# wifischematic.net
KiCad netlist of a schematic drawn in EAGLE
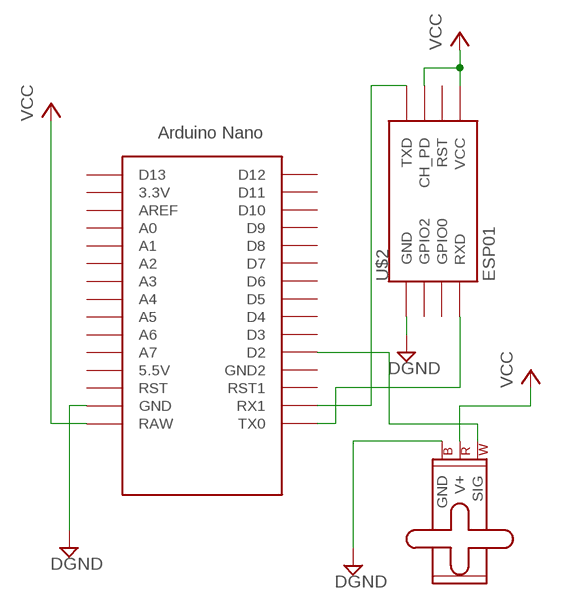
[diagram p0: schematic, sheet 1]

(export (version "E")
  (design (tool "Eeschema 10.0.6"))
  (components
    (comp (ref "M1")
      (value "SMALL_SERVO")
      (footprint "eagle-import:1X03")
      (libsource (lib "eagle-import") (part "SMALL_SERVO"))
    )
    (comp (ref "U$1")
      (value "NANO")
      (footprint "eagle-import:NANO")
      (libsource (lib "eagle-import") (part "NANO"))
    )
    (comp (ref "U$2")
      (value "ESP01")
      (footprint "eagle-import:ESP01")
      (libsource (lib "eagle-import") (part "ESP01"))
    )
  )
  (nets
    (net (code "1") (name "DGND") (class "Default")
      (node (ref "M1") (pin "3") (pinfunction "GND_3") (pintype "bidirectional"))
      (node (ref "U$1") (pin "GND") (pinfunction "GND_GND") (pintype "bidirectional"))
      (node (ref "U$2") (pin "GND") (pinfunction "GND_GND") (pintype "bidirectional"))
    )
    (net (code "2") (name "Net-(M1-SIG)") (class "Default")
      (node (ref "M1") (pin "1") (pinfunction "SIG_1") (pintype "bidirectional"))
      (node (ref "U$1") (pin "D2") (pinfunction "D2_D2") (pintype "bidirectional"))
    )
    (net (code "3") (name "Net-(U$2-RXD)") (class "Default")
      (node (ref "U$1") (pin "TX0") (pinfunction "TX0_TX0") (pintype "bidirectional"))
      (node (ref "U$2") (pin "RX") (pinfunction "RXD_RX") (pintype "bidirectional"))
    )
    (net (code "4") (name "Net-(U$2-TXD)") (class "Default")
      (node (ref "U$1") (pin "RX1") (pinfunction "RX1_RX1") (pintype "bidirectional"))
      (node (ref "U$2") (pin "TX") (pinfunction "TXD_TX") (pintype "bidirectional"))
    )
    (net (code "5") (name "VCC") (class "Default")
      (node (ref "M1") (pin "2") (pinfunction "V+_2") (pintype "bidirectional"))
      (node (ref "U$1") (pin "RAW") (pinfunction "RAW_RAW") (pintype "bidirectional"))
      (node (ref "U$2") (pin "CH_PD") (pinfunction "CH_PD_CH_PD") (pintype "bidirectional"))
      (node (ref "U$2") (pin "VCC") (pinfunction "VCC_VCC") (pintype "bidirectional"))
    )
    (net (code "6") (name "unconnected-(U$1-5.5V-Pad5V)") (class "Default")
      (node (ref "U$1") (pin "5V") (pinfunction "5.5V_5V") (pintype "bidirectional"))
    )
    (net (code "7") (name "unconnected-(U$1-GND2-PadGND1)") (class "Default")
      (node (ref "U$1") (pin "GND1") (pinfunction "GND2_GND1") (pintype "bidirectional"))
    )
    (net (code "8") (name "unconnected-(U$1-Pad3.3V)") (class "Default")
      (node (ref "U$1") (pin "3.3V") (pinfunction "3.3V_3.3V") (pintype "bidirectional"))
    )
    (net (code "9") (name "unconnected-(U$1-PadA0)") (class "Default")
      (node (ref "U$1") (pin "A0") (pinfunction "A0_A0") (pintype "bidirectional"))
    )
    (net (code "10") (name "unconnected-(U$1-PadA1)") (class "Default")
      (node (ref "U$1") (pin "A1") (pinfunction "A1_A1") (pintype "bidirectional"))
    )
    (net (code "11") (name "unconnected-(U$1-PadA2)") (class "Default")
      (node (ref "U$1") (pin "A2") (pinfunction "A2_A2") (pintype "bidirectional"))
    )
    (net (code "12") (name "unconnected-(U$1-PadA3)") (class "Default")
      (node (ref "U$1") (pin "A3") (pinfunction "A3_A3") (pintype "bidirectional"))
    )
    (net (code "13") (name "unconnected-(U$1-PadA4)") (class "Default")
      (node (ref "U$1") (pin "A4") (pinfunction "A4_A4") (pintype "bidirectional"))
    )
    (net (code "14") (name "unconnected-(U$1-PadA5)") (class "Default")
      (node (ref "U$1") (pin "A5") (pinfunction "A5_A5") (pintype "bidirectional"))
    )
    (net (code "15") (name "unconnected-(U$1-PadA6)") (class "Default")
      (node (ref "U$1") (pin "A6") (pinfunction "A6_A6") (pintype "bidirectional"))
    )
    (net (code "16") (name "unconnected-(U$1-PadA7)") (class "Default")
      (node (ref "U$1") (pin "A7") (pinfunction "A7_A7") (pintype "bidirectional"))
    )
    (net (code "17") (name "unconnected-(U$1-PadAREF)") (class "Default")
      (node (ref "U$1") (pin "AREF") (pinfunction "AREF_AREF") (pintype "bidirectional"))
    )
    (net (code "18") (name "unconnected-(U$1-PadD3)") (class "Default")
      (node (ref "U$1") (pin "D3") (pinfunction "D3_D3") (pintype "bidirectional"))
    )
    (net (code "19") (name "unconnected-(U$1-PadD4)") (class "Default")
      (node (ref "U$1") (pin "D4") (pinfunction "D4_D4") (pintype "bidirectional"))
    )
    (net (code "20") (name "unconnected-(U$1-PadD5)") (class "Default")
      (node (ref "U$1") (pin "D5") (pinfunction "D5_D5") (pintype "bidirectional"))
    )
    (net (code "21") (name "unconnected-(U$1-PadD6)") (class "Default")
      (node (ref "U$1") (pin "D6") (pinfunction "D6_D6") (pintype "bidirectional"))
    )
    (net (code "22") (name "unconnected-(U$1-PadD7)") (class "Default")
      (node (ref "U$1") (pin "D7") (pinfunction "D7_D7") (pintype "bidirectional"))
    )
    (net (code "23") (name "unconnected-(U$1-PadD8)") (class "Default")
      (node (ref "U$1") (pin "D8") (pinfunction "D8_D8") (pintype "bidirectional"))
    )
    (net (code "24") (name "unconnected-(U$1-PadD9)") (class "Default")
      (node (ref "U$1") (pin "D9") (pinfunction "D9_D9") (pintype "bidirectional"))
    )
    (net (code "25") (name "unconnected-(U$1-PadD10)") (class "Default")
      (node (ref "U$1") (pin "D10") (pinfunction "D10_D10") (pintype "bidirectional"))
    )
    (net (code "26") (name "unconnected-(U$1-PadD11)") (class "Default")
      (node (ref "U$1") (pin "D11") (pinfunction "D11_D11") (pintype "bidirectional"))
    )
    (net (code "27") (name "unconnected-(U$1-PadD12)") (class "Default")
      (node (ref "U$1") (pin "D12") (pinfunction "D12_D12") (pintype "bidirectional"))
    )
    (net (code "28") (name "unconnected-(U$1-PadD13)") (class "Default")
      (node (ref "U$1") (pin "D13") (pinfunction "D13_D13") (pintype "bidirectional"))
    )
    (net (code "29") (name "unconnected-(U$1-PadICSP1)") (class "Default")
      (node (ref "U$1") (pin "ICSP1") (pinfunction "ICSP1_ICSP1") (pintype "bidirectional"))
    )
    (net (code "30") (name "unconnected-(U$1-PadICSP2)") (class "Default")
      (node (ref "U$1") (pin "ICSP2") (pinfunction "ICSP2_ICSP2") (pintype "bidirectional"))
    )
    (net (code "31") (name "unconnected-(U$1-PadICSP3)") (class "Default")
      (node (ref "U$1") (pin "ICSP3") (pinfunction "ICSP3_ICSP3") (pintype "bidirectional"))
    )
    (net (code "32") (name "unconnected-(U$1-PadICSP4)") (class "Default")
      (node (ref "U$1") (pin "ICSP4") (pinfunction "ICSP4_ICSP4") (pintype "bidirectional"))
    )
    (net (code "33") (name "unconnected-(U$1-PadICSP5)") (class "Default")
      (node (ref "U$1") (pin "ICSP5") (pinfunction "ICSP5_ICSP5") (pintype "bidirectional"))
    )
    (net (code "34") (name "unconnected-(U$1-PadICSP6)") (class "Default")
      (node (ref "U$1") (pin "ICSP6") (pinfunction "ICSP6_ICSP6") (pintype "bidirectional"))
    )
    (net (code "35") (name "unconnected-(U$1-PadRST)") (class "Default")
      (node (ref "U$1") (pin "RST") (pinfunction "RST_RST") (pintype "bidirectional"))
    )
    (net (code "36") (name "unconnected-(U$1-PadRST1)") (class "Default")
      (node (ref "U$1") (pin "RST1") (pinfunction "RST1_RST1") (pintype "bidirectional"))
    )
    (net (code "37") (name "unconnected-(U$2-PadGPIO0)") (class "Default")
      (node (ref "U$2") (pin "GPIO0") (pinfunction "GPIO0_GPIO0") (pintype "bidirectional"))
    )
    (net (code "38") (name "unconnected-(U$2-PadGPIO2)") (class "Default")
      (node (ref "U$2") (pin "GPIO2") (pinfunction "GPIO2_GPIO2") (pintype "bidirectional"))
    )
    (net (code "39") (name "unconnected-(U$2-PadRST)") (class "Default")
      (node (ref "U$2") (pin "RST") (pinfunction "RST_RST") (pintype "bidirectional"))
    )
  )
)
